# Motor_d.net
KiCad netlist of a schematic drawn in Altium Designer
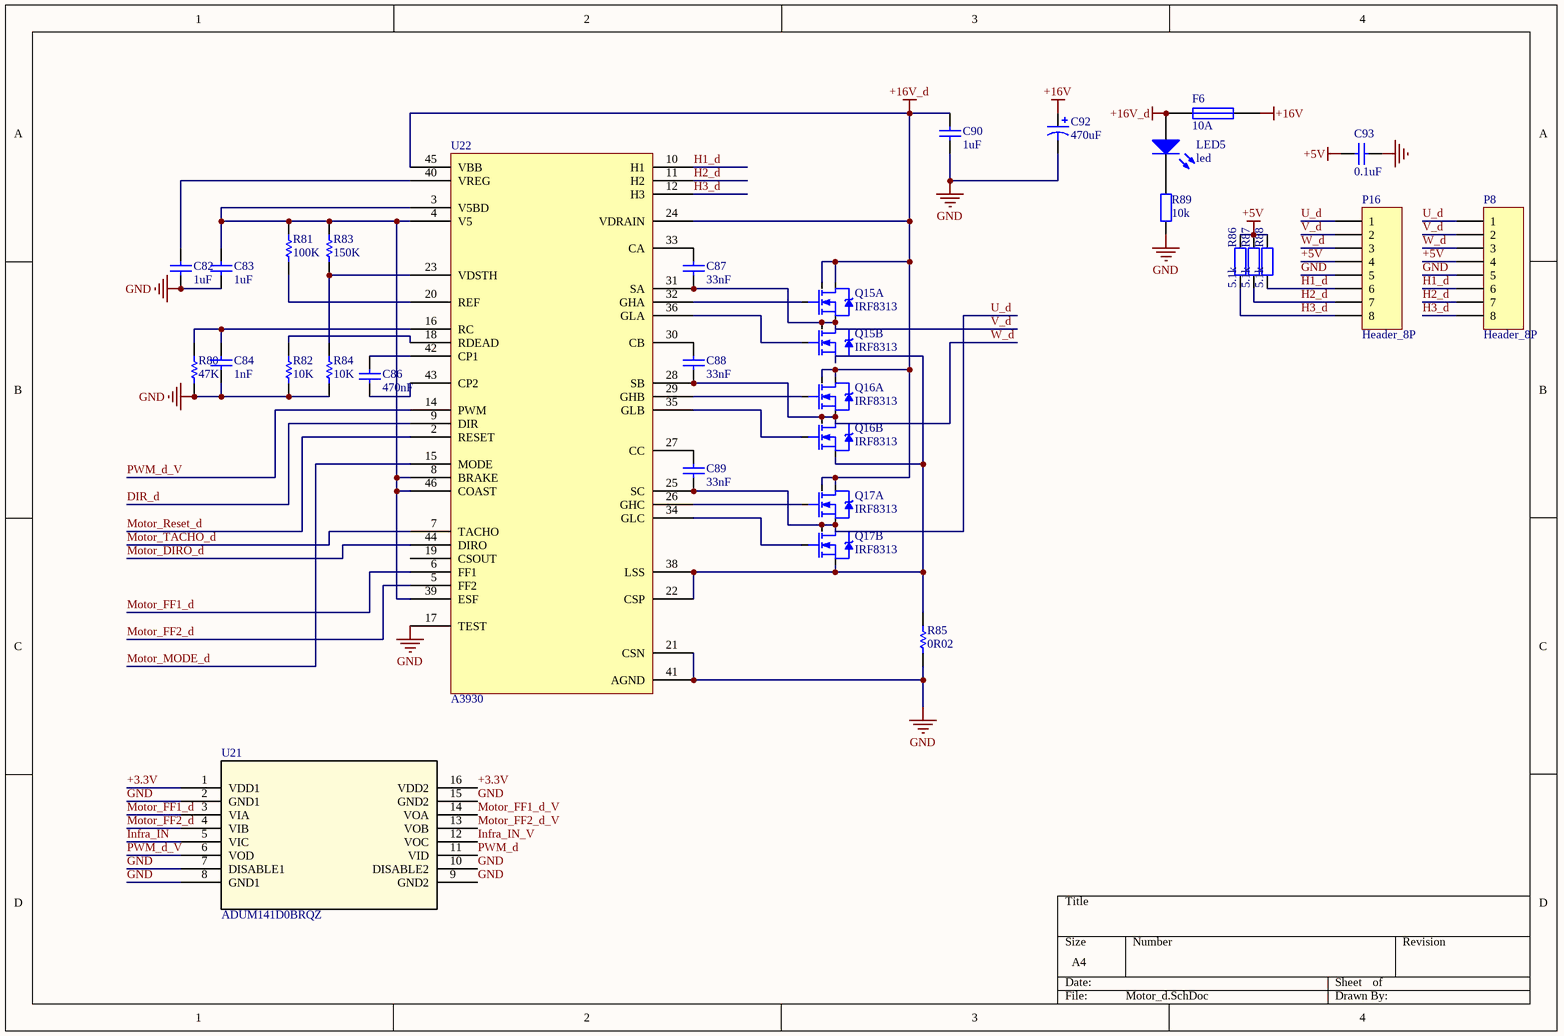
[diagram p0: Motor_d.SchDoc]

(export (version "E")
  (design (tool "Eeschema 10.0.6"))
  (components
    (comp (ref "C82")
      (value "1uF")
      (footprint "0603C")
      (description "Capacitor")
      (fields
        (field (name "MANUFACTURER") "Generic Components")
        (field (name "Comment") "1uf")
        (field (name "PUBLISHER") "Altium Hobart Technology Centre")
      )
      (libsource (lib "hp_2018_03") (part "Cap"))
    )
    (comp (ref "C83")
      (value "1uF")
      (footprint "0603C")
      (description "Capacitor")
      (fields
        (field (name "MANUFACTURER") "Generic Components")
        (field (name "Comment") "1uf")
        (field (name "PUBLISHER") "Altium Hobart Technology Centre")
      )
      (libsource (lib "hp_2018_03") (part "Cap"))
    )
    (comp (ref "C84")
      (value "1nF")
      (footprint "0603C")
      (description "Capacitor")
      (fields
        (field (name "MANUFACTURER") "Generic Components")
        (field (name "Comment") "1nf")
        (field (name "PUBLISHER") "Altium Hobart Technology Centre")
      )
      (libsource (lib "hp_2018_03") (part "Cap"))
    )
    (comp (ref "C86")
      (value "470nF")
      (footprint "0603C")
      (description "Capacitor")
      (fields
        (field (name "MANUFACTURER") "Generic Components")
        (field (name "Comment") "470nf")
        (field (name "PUBLISHER") "Altium Hobart Technology Centre")
      )
      (libsource (lib "hp_2018_03") (part "Cap"))
    )
    (comp (ref "C87")
      (value "33nF")
      (footprint "0603C")
      (description "Capacitor")
      (fields
        (field (name "MANUFACTURER") "Generic Components")
        (field (name "Comment") "33nf")
        (field (name "PUBLISHER") "Altium Hobart Technology Centre")
      )
      (libsource (lib "hp_2018_03") (part "Cap"))
    )
    (comp (ref "C88")
      (value "33nF")
      (footprint "0603C")
      (description "Capacitor")
      (fields
        (field (name "MANUFACTURER") "Generic Components")
        (field (name "Comment") "33nf")
        (field (name "PUBLISHER") "Altium Hobart Technology Centre")
      )
      (libsource (lib "hp_2018_03") (part "Cap"))
    )
    (comp (ref "C89")
      (value "33nF")
      (footprint "0603C")
      (description "Capacitor")
      (fields
        (field (name "MANUFACTURER") "Generic Components")
        (field (name "Comment") "33nf")
        (field (name "PUBLISHER") "Altium Hobart Technology Centre")
      )
      (libsource (lib "hp_2018_03") (part "Cap"))
    )
    (comp (ref "C90")
      (value "1uF")
      (footprint "0603C")
      (description "Capacitor")
      (fields
        (field (name "MANUFACTURER") "Generic Components")
        (field (name "Comment") "1uf")
        (field (name "PUBLISHER") "Altium Hobart Technology Centre")
      )
      (libsource (lib "hp_2018_03") (part "Cap"))
    )
    (comp (ref "C92")
      (value "470uF")
      (footprint "470uF")
      (description "Polarized Capacitor (Radial)")
      (fields (field (name "PUBLISHER") "Altium Limited"))
      (libsource (lib "Miscellaneous Devices") (part "Cap Pol1"))
    )
    (comp (ref "C93")
      (value "0.1uF")
      (footprint "0603C")
      (description "Capacitor")
      (fields
        (field (name "MANUFACTURER") "Generic Components")
        (field (name "Comment") "0.1uf")
        (field (name "PUBLISHER") "Altium Hobart Technology Centre")
      )
      (libsource (lib "hp_2018_03") (part "Cap"))
    )
    (comp (ref "F6")
      (value "10A")
      (footprint "Main_Board:FUSE_HEADER")
      (libsource (lib "Integrated_Library2") (part "FUSE"))
    )
    (comp (ref "LED5")
      (value "led")
      (footprint "0603_diode")
      (libsource (lib "Integrated_Library2") (part "led"))
    )
    (comp (ref "P8")
      (value "Header_8P")
      (footprint "8P - WF25122")
      (description "Used for Motor connection in ZJUNlict")
      (libsource (lib "Integrated_Library2") (part "Header_8P"))
    )
    (comp (ref "P16")
      (value "Header_8P")
      (footprint "SHDR8")
      (description "Used for Motor connection in ZJUNlict")
      (libsource (lib "Integrated_Library2") (part "Header_8P"))
    )
    (comp (ref "Q15") (value "IRF8313") (footprint "so-8 bg") (libsource (lib "BLDC") (part "SO-8 IRF8313")))
    (comp (ref "Q16") (value "IRF8313") (footprint "so-8 bg") (libsource (lib "BLDC") (part "SO-8 IRF8313")))
    (comp (ref "Q17") (value "IRF8313") (footprint "so-8 bg") (libsource (lib "BLDC") (part "SO-8 IRF8313")))
    (comp (ref "R80")
      (value "47K")
      (footprint "0603R")
      (description "Resistor")
      (fields
        (field (name "MANUFACTURER") "Generic Components")
        (field (name "Comment") "47k")
        (field (name "PUBLISHER") "Altium Hobart Technology Centre")
      )
      (libsource (lib "hp_2018_03") (part "Res1"))
    )
    (comp (ref "R81")
      (value "100K")
      (footprint "0603R")
      (description "Resistor")
      (fields
        (field (name "MANUFACTURER") "Generic Components")
        (field (name "Comment") "100k")
        (field (name "PUBLISHER") "Altium Hobart Technology Centre")
      )
      (libsource (lib "hp_2018_03") (part "Res1"))
    )
    (comp (ref "R82")
      (value "10K")
      (footprint "0603R")
      (description "Resistor")
      (fields
        (field (name "MANUFACTURER") "Generic Components")
        (field (name "Comment") "10k")
        (field (name "PUBLISHER") "Altium Hobart Technology Centre")
      )
      (libsource (lib "hp_2018_03") (part "Res1"))
    )
    (comp (ref "R83")
      (value "150K")
      (footprint "0603R")
      (description "Resistor")
      (fields
        (field (name "MANUFACTURER") "Generic Components")
        (field (name "Comment") "100k")
        (field (name "PUBLISHER") "Altium Hobart Technology Centre")
      )
      (libsource (lib "hp_2018_03") (part "Res1"))
    )
    (comp (ref "R84")
      (value "10K")
      (footprint "0603R")
      (description "Resistor")
      (fields
        (field (name "MANUFACTURER") "Generic Components")
        (field (name "Comment") "10k")
        (field (name "PUBLISHER") "Altium Hobart Technology Centre")
      )
      (libsource (lib "hp_2018_03") (part "Res1"))
    )
    (comp (ref "R85")
      (value "0R02")
      (footprint "1206 10A")
      (description "Resistor")
      (fields
        (field (name "MANUFACTURER") "Generic Components")
        (field (name "Comment") "0.02")
        (field (name "PUBLISHER") "Altium Hobart Technology Centre")
      )
      (libsource (lib "hp_2018_03") (part "Res1"))
    )
    (comp (ref "R86") (value "5.1k") (footprint "0805") (libsource (lib "Integrated_Library2") (part "res")))
    (comp (ref "R87") (value "5.1k") (footprint "0805") (libsource (lib "Integrated_Library2") (part "res")))
    (comp (ref "R88") (value "5.1k") (footprint "0805") (libsource (lib "Integrated_Library2") (part "res")))
    (comp (ref "R89") (value "10k") (footprint "0603") (libsource (lib "") (part "res_1")))
    (comp (ref "U21")
      (value "ADUM141D0BRQZ")
      (footprint "Main_Board:RQ_16")
      (description "Imported")
      (libsource (lib "Main_Board") (part "ADUM141D0BRQZ"))
    )
    (comp (ref "U22") (value "A3930") (footprint "LQFP-48") (libsource (lib "BLDC") (part "LQFP 48")))
  )
  (nets
    (net (code "1") (name "+5V") (class "Default")
      (node (ref "C93") (pin "2") (pinfunction "2_2") (pintype "passive"))
      (node (ref "P16") (pin "4") (pinfunction "4_4") (pintype "passive"))
      (node (ref "P8") (pin "4") (pinfunction "4_4") (pintype "passive"))
      (node (ref "R86") (pin "1") (pinfunction "1_1") (pintype "passive"))
      (node (ref "R87") (pin "1") (pinfunction "1_1") (pintype "passive"))
      (node (ref "R88") (pin "1") (pinfunction "1_1") (pintype "passive"))
    )
    (net (code "2") (name "+16V") (class "Default")
      (node (ref "C92") (pin "1") (pinfunction "1_1") (pintype "passive"))
      (node (ref "F6") (pin "1") (pinfunction "1_1") (pintype "passive"))
    )
    (net (code "3") (name "+16V_d") (class "Default")
      (node (ref "C90") (pin "2") (pinfunction "2_2") (pintype "passive"))
      (node (ref "F6") (pin "2") (pinfunction "2_2") (pintype "passive"))
      (node (ref "LED5") (pin "1") (pinfunction "A_1") (pintype "passive"))
      (node (ref "Q15") (pin "7") (pinfunction "D2_7") (pintype "passive"))
      (node (ref "Q15") (pin "8") (pinfunction "D2_8") (pintype "passive"))
      (node (ref "Q16") (pin "7") (pinfunction "D2_7") (pintype "passive"))
      (node (ref "Q16") (pin "8") (pinfunction "D2_8") (pintype "passive"))
      (node (ref "Q17") (pin "7") (pinfunction "D2_7") (pintype "passive"))
      (node (ref "Q17") (pin "8") (pinfunction "D2_8") (pintype "passive"))
      (node (ref "U22") (pin "24") (pinfunction "VDRAIN_24") (pintype "passive"))
      (node (ref "U22") (pin "45") (pinfunction "VBB_45") (pintype "passive"))
    )
    (net (code "4") (name "/+3.3V") (class "Default")
      (node (ref "U21") (pin "1") (pinfunction "VDD1_1") (pintype "passive"))
      (node (ref "U21") (pin "16") (pinfunction "VDD2_16") (pintype "passive"))
    )
    (net (code "5") (name "/DIR_d") (class "Default")
      (node (ref "U22") (pin "9") (pinfunction "DIR_9") (pintype "passive"))
    )
    (net (code "6") (name "/H1_d") (class "Default")
      (node (ref "P16") (pin "6") (pinfunction "6_6") (pintype "passive"))
      (node (ref "P8") (pin "6") (pinfunction "6_6") (pintype "passive"))
      (node (ref "R88") (pin "2") (pinfunction "2_2") (pintype "passive"))
      (node (ref "U22") (pin "10") (pinfunction "H1_10") (pintype "passive"))
    )
    (net (code "7") (name "/H2_d") (class "Default")
      (node (ref "P16") (pin "7") (pinfunction "7_7") (pintype "passive"))
      (node (ref "P8") (pin "7") (pinfunction "7_7") (pintype "passive"))
      (node (ref "R87") (pin "2") (pinfunction "2_2") (pintype "passive"))
      (node (ref "U22") (pin "11") (pinfunction "H2_11") (pintype "passive"))
    )
    (net (code "8") (name "/H3_d") (class "Default")
      (node (ref "P16") (pin "8") (pinfunction "8_8") (pintype "passive"))
      (node (ref "P8") (pin "8") (pinfunction "8_8") (pintype "passive"))
      (node (ref "R86") (pin "2") (pinfunction "2_2") (pintype "passive"))
      (node (ref "U22") (pin "12") (pinfunction "H3_12") (pintype "passive"))
    )
    (net (code "9") (name "/Infra_IN") (class "Default")
      (node (ref "U21") (pin "5") (pinfunction "VIC_5") (pintype "passive"))
    )
    (net (code "10") (name "/Infra_IN_V") (class "Default")
      (node (ref "U21") (pin "12") (pinfunction "VOC_12") (pintype "passive"))
    )
    (net (code "11") (name "/Motor_DIRO_d") (class "Default")
      (node (ref "U22") (pin "44") (pinfunction "DIRO_44") (pintype "passive"))
    )
    (net (code "12") (name "/Motor_FF1_d") (class "Default")
      (node (ref "U21") (pin "3") (pinfunction "VIA_3") (pintype "passive"))
      (node (ref "U22") (pin "6") (pinfunction "FF1_6") (pintype "passive"))
    )
    (net (code "13") (name "/Motor_FF1_d_V") (class "Default")
      (node (ref "U21") (pin "14") (pinfunction "VOA_14") (pintype "passive"))
    )
    (net (code "14") (name "/Motor_FF2_d") (class "Default")
      (node (ref "U21") (pin "4") (pinfunction "VIB_4") (pintype "passive"))
      (node (ref "U22") (pin "5") (pinfunction "FF2_5") (pintype "passive"))
    )
    (net (code "15") (name "/Motor_FF2_d_V") (class "Default")
      (node (ref "U21") (pin "13") (pinfunction "VOB_13") (pintype "passive"))
    )
    (net (code "16") (name "/Motor_MODE_d") (class "Default")
      (node (ref "U22") (pin "15") (pinfunction "MODE_15") (pintype "passive"))
    )
    (net (code "17") (name "/Motor_Reset_d") (class "Default")
      (node (ref "U22") (pin "2") (pinfunction "RESET_2") (pintype "passive"))
    )
    (net (code "18") (name "/Motor_TACHO_d") (class "Default")
      (node (ref "U22") (pin "7") (pinfunction "TACHO_7") (pintype "passive"))
    )
    (net (code "19") (name "/PWM_d") (class "Default")
      (node (ref "U21") (pin "11") (pinfunction "VID_11") (pintype "passive"))
    )
    (net (code "20") (name "/PWM_d_V") (class "Default")
      (node (ref "U21") (pin "6") (pinfunction "VOD_6") (pintype "passive"))
      (node (ref "U22") (pin "14") (pinfunction "PWM_14") (pintype "passive"))
    )
    (net (code "21") (name "/U_d") (class "Default")
      (node (ref "C89") (pin "1") (pinfunction "1_1") (pintype "passive"))
      (node (ref "P16") (pin "1") (pinfunction "1_1") (pintype "passive"))
      (node (ref "P8") (pin "1") (pinfunction "1_1") (pintype "passive"))
      (node (ref "Q17") (pin "1") (pinfunction "S2_1") (pintype "passive"))
      (node (ref "Q17") (pin "5") (pinfunction "D1_5") (pintype "passive"))
      (node (ref "Q17") (pin "6") (pinfunction "D1_6") (pintype "passive"))
      (node (ref "U22") (pin "25") (pinfunction "SC_25") (pintype "passive"))
    )
    (net (code "22") (name "/V_d") (class "Default")
      (node (ref "C87") (pin "1") (pinfunction "1_1") (pintype "passive"))
      (node (ref "P16") (pin "2") (pinfunction "2_2") (pintype "passive"))
      (node (ref "P8") (pin "2") (pinfunction "2_2") (pintype "passive"))
      (node (ref "Q15") (pin "1") (pinfunction "S2_1") (pintype "passive"))
      (node (ref "Q15") (pin "5") (pinfunction "D1_5") (pintype "passive"))
      (node (ref "Q15") (pin "6") (pinfunction "D1_6") (pintype "passive"))
      (node (ref "U22") (pin "31") (pinfunction "SA_31") (pintype "passive"))
    )
    (net (code "23") (name "/W_d") (class "Default")
      (node (ref "C88") (pin "1") (pinfunction "1_1") (pintype "passive"))
      (node (ref "P16") (pin "3") (pinfunction "3_3") (pintype "passive"))
      (node (ref "P8") (pin "3") (pinfunction "3_3") (pintype "passive"))
      (node (ref "Q16") (pin "1") (pinfunction "S2_1") (pintype "passive"))
      (node (ref "Q16") (pin "5") (pinfunction "D1_5") (pintype "passive"))
      (node (ref "Q16") (pin "6") (pinfunction "D1_6") (pintype "passive"))
      (node (ref "U22") (pin "28") (pinfunction "SB_28") (pintype "passive"))
    )
    (net (code "24") (name "GND") (class "Default")
      (node (ref "C82") (pin "1") (pinfunction "1_1") (pintype "passive"))
      (node (ref "C83") (pin "1") (pinfunction "1_1") (pintype "passive"))
      (node (ref "C84") (pin "1") (pinfunction "1_1") (pintype "passive"))
      (node (ref "C90") (pin "1") (pinfunction "1_1") (pintype "passive"))
      (node (ref "C92") (pin "2") (pinfunction "2_2") (pintype "passive"))
      (node (ref "C93") (pin "1") (pinfunction "1_1") (pintype "passive"))
      (node (ref "P16") (pin "5") (pinfunction "5_5") (pintype "passive"))
      (node (ref "P8") (pin "5") (pinfunction "5_5") (pintype "passive"))
      (node (ref "R80") (pin "1") (pinfunction "1_1") (pintype "passive"))
      (node (ref "R82") (pin "1") (pinfunction "1_1") (pintype "passive"))
      (node (ref "R84") (pin "1") (pinfunction "1_1") (pintype "passive"))
      (node (ref "R85") (pin "1") (pinfunction "1_1") (pintype "passive"))
      (node (ref "R89") (pin "1") (pinfunction "1_1") (pintype "passive"))
      (node (ref "U21") (pin "10") (pinfunction "DISABLE2_10") (pintype "passive"))
      (node (ref "U21") (pin "15") (pinfunction "GND2_15") (pintype "passive"))
      (node (ref "U21") (pin "2") (pinfunction "GND1_2") (pintype "passive"))
      (node (ref "U21") (pin "7") (pinfunction "DISABLE1_7") (pintype "passive"))
      (node (ref "U21") (pin "8") (pinfunction "GND1_8") (pintype "passive"))
      (node (ref "U21") (pin "9") (pinfunction "GND2_9") (pintype "passive"))
      (node (ref "U22") (pin "17") (pinfunction "TEST_17") (pintype "passive"))
      (node (ref "U22") (pin "21") (pinfunction "CSN_21") (pintype "passive"))
      (node (ref "U22") (pin "41") (pinfunction "AGND_41") (pintype "passive"))
    )
    (net (code "25") (name "Net-(LED5-K)") (class "Default")
      (node (ref "LED5") (pin "2") (pinfunction "K_2") (pintype "passive"))
      (node (ref "R89") (pin "2") (pinfunction "2_2") (pintype "passive"))
    )
    (net (code "26") (name "Net-(Q15A-G2)") (class "Default")
      (node (ref "Q15") (pin "2") (pinfunction "G2_2") (pintype "passive"))
      (node (ref "U22") (pin "32") (pinfunction "GHA_32") (pintype "passive"))
    )
    (net (code "27") (name "Net-(Q15B-G1)") (class "Default")
      (node (ref "Q15") (pin "4") (pinfunction "G1_4") (pintype "passive"))
      (node (ref "U22") (pin "36") (pinfunction "GLA_36") (pintype "passive"))
    )
    (net (code "28") (name "Net-(Q15B-S1)") (class "Default")
      (node (ref "Q15") (pin "3") (pinfunction "S1_3") (pintype "passive"))
      (node (ref "Q16") (pin "3") (pinfunction "S1_3") (pintype "passive"))
      (node (ref "Q17") (pin "3") (pinfunction "S1_3") (pintype "passive"))
      (node (ref "R85") (pin "2") (pinfunction "2_2") (pintype "passive"))
      (node (ref "U22") (pin "22") (pinfunction "CSP_22") (pintype "passive"))
      (node (ref "U22") (pin "38") (pinfunction "LSS_38") (pintype "passive"))
    )
    (net (code "29") (name "Net-(Q16A-G2)") (class "Default")
      (node (ref "Q16") (pin "2") (pinfunction "G2_2") (pintype "passive"))
      (node (ref "U22") (pin "29") (pinfunction "GHB_29") (pintype "passive"))
    )
    (net (code "30") (name "Net-(Q16B-G1)") (class "Default")
      (node (ref "Q16") (pin "4") (pinfunction "G1_4") (pintype "passive"))
      (node (ref "U22") (pin "35") (pinfunction "GLB_35") (pintype "passive"))
    )
    (net (code "31") (name "Net-(Q17A-G2)") (class "Default")
      (node (ref "Q17") (pin "2") (pinfunction "G2_2") (pintype "passive"))
      (node (ref "U22") (pin "26") (pinfunction "GHC_26") (pintype "passive"))
    )
    (net (code "32") (name "Net-(Q17B-G1)") (class "Default")
      (node (ref "Q17") (pin "4") (pinfunction "G1_4") (pintype "passive"))
      (node (ref "U22") (pin "34") (pinfunction "GLC_34") (pintype "passive"))
    )
    (net (code "33") (name "Net-(U22-BRAKE)") (class "Default")
      (node (ref "C83") (pin "2") (pinfunction "2_2") (pintype "passive"))
      (node (ref "R81") (pin "2") (pinfunction "2_2") (pintype "passive"))
      (node (ref "R83") (pin "2") (pinfunction "2_2") (pintype "passive"))
      (node (ref "U22") (pin "3") (pinfunction "V5BD_3") (pintype "passive"))
      (node (ref "U22") (pin "39") (pinfunction "ESF_39") (pintype "passive"))
      (node (ref "U22") (pin "4") (pinfunction "V5_4") (pintype "passive"))
      (node (ref "U22") (pin "46") (pinfunction "COAST_46") (pintype "passive"))
      (node (ref "U22") (pin "8") (pinfunction "BRAKE_8") (pintype "passive"))
    )
    (net (code "34") (name "Net-(U22-CA)") (class "Default")
      (node (ref "C87") (pin "2") (pinfunction "2_2") (pintype "passive"))
      (node (ref "U22") (pin "33") (pinfunction "CA_33") (pintype "passive"))
    )
    (net (code "35") (name "Net-(U22-CB)") (class "Default")
      (node (ref "C88") (pin "2") (pinfunction "2_2") (pintype "passive"))
      (node (ref "U22") (pin "30") (pinfunction "CB_30") (pintype "passive"))
    )
    (net (code "36") (name "Net-(U22-CC)") (class "Default")
      (node (ref "C89") (pin "2") (pinfunction "2_2") (pintype "passive"))
      (node (ref "U22") (pin "27") (pinfunction "CC_27") (pintype "passive"))
    )
    (net (code "37") (name "Net-(U22-CP1)") (class "Default")
      (node (ref "C86") (pin "2") (pinfunction "2_2") (pintype "passive"))
      (node (ref "U22") (pin "42") (pinfunction "CP1_42") (pintype "passive"))
    )
    (net (code "38") (name "Net-(U22-CP2)") (class "Default")
      (node (ref "C86") (pin "1") (pinfunction "1_1") (pintype "passive"))
      (node (ref "U22") (pin "43") (pinfunction "CP2_43") (pintype "passive"))
    )
    (net (code "39") (name "Net-(U22-RC)") (class "Default")
      (node (ref "C84") (pin "2") (pinfunction "2_2") (pintype "passive"))
      (node (ref "R80") (pin "2") (pinfunction "2_2") (pintype "passive"))
      (node (ref "U22") (pin "16") (pinfunction "RC_16") (pintype "passive"))
    )
    (net (code "40") (name "Net-(U22-RDEAD)") (class "Default")
      (node (ref "R82") (pin "2") (pinfunction "2_2") (pintype "passive"))
      (node (ref "U22") (pin "18") (pinfunction "RDEAD_18") (pintype "passive"))
    )
    (net (code "41") (name "Net-(U22-REF)") (class "Default")
      (node (ref "R81") (pin "1") (pinfunction "1_1") (pintype "passive"))
      (node (ref "U22") (pin "20") (pinfunction "REF_20") (pintype "passive"))
    )
    (net (code "42") (name "Net-(U22-VDSTH)") (class "Default")
      (node (ref "R83") (pin "1") (pinfunction "1_1") (pintype "passive"))
      (node (ref "R84") (pin "2") (pinfunction "2_2") (pintype "passive"))
      (node (ref "U22") (pin "23") (pinfunction "VDSTH_23") (pintype "passive"))
    )
    (net (code "43") (name "Net-(U22-VREG)") (class "Default")
      (node (ref "C82") (pin "2") (pinfunction "2_2") (pintype "passive"))
      (node (ref "U22") (pin "40") (pinfunction "VREG_40") (pintype "passive"))
    )
    (net (code "44") (name "unconnected-(U22-CSOUT-Pad19)") (class "Default")
      (node (ref "U22") (pin "19") (pinfunction "CSOUT_19") (pintype "passive"))
    )
  )
)
